# Micromouse.net
KiCad netlist of a schematic drawn in EAGLE
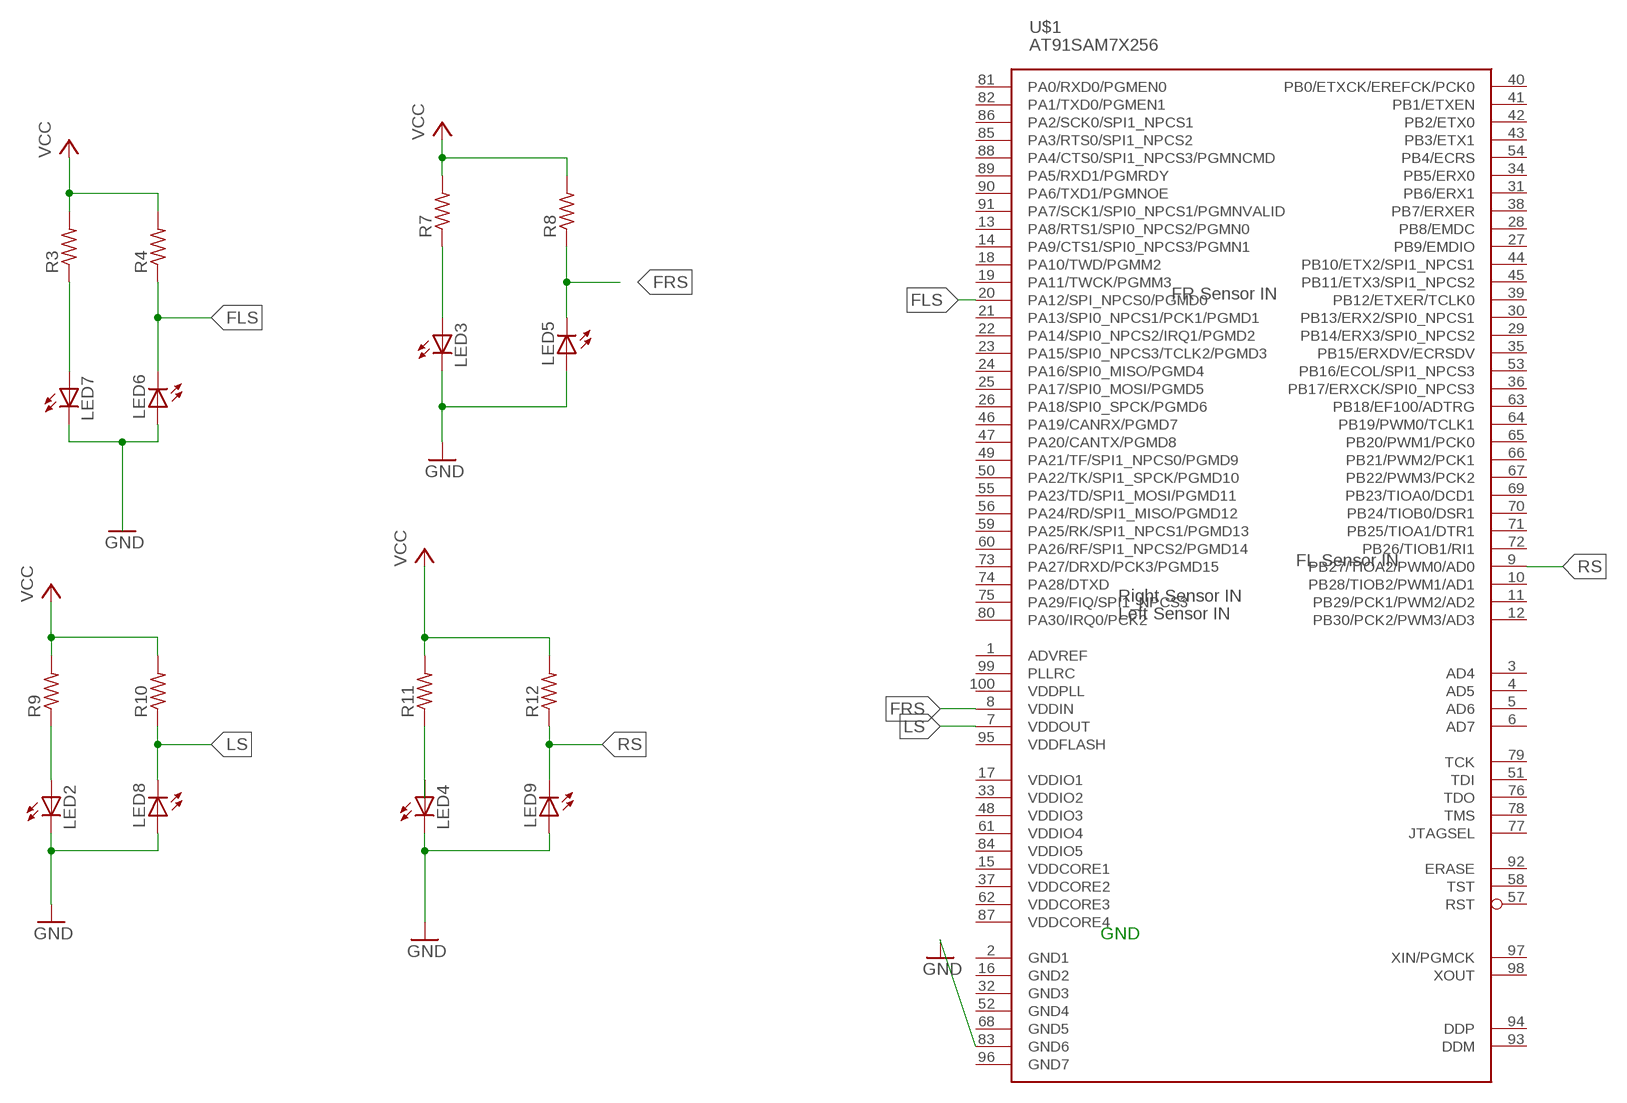
[diagram p0: schematic, sheet 1]

(export (version "E")
  (design (tool "Eeschema 10.0.6"))
  (components
    (comp (ref "LED2")
      (value "LED5MM")
      (footprint "eagle-import:LED5MM")
      (libsource (lib "eagle-import") (part "LED5MM"))
    )
    (comp (ref "LED3")
      (value "LED5MM")
      (footprint "eagle-import:LED5MM")
      (libsource (lib "eagle-import") (part "LED5MM"))
    )
    (comp (ref "LED4")
      (value "LED5MM")
      (footprint "eagle-import:LED5MM")
      (libsource (lib "eagle-import") (part "LED5MM"))
    )
    (comp (ref "LED5")
      (value "LED5MM")
      (footprint "eagle-import:LED5MM")
      (libsource (lib "eagle-import") (part "LED5MM"))
    )
    (comp (ref "LED6")
      (value "LED5MM")
      (footprint "eagle-import:LED5MM")
      (libsource (lib "eagle-import") (part "LED5MM"))
    )
    (comp (ref "LED7")
      (value "LED5MM")
      (footprint "eagle-import:LED5MM")
      (libsource (lib "eagle-import") (part "LED5MM"))
    )
    (comp (ref "LED8")
      (value "LED5MM")
      (footprint "eagle-import:LED5MM")
      (libsource (lib "eagle-import") (part "LED5MM"))
    )
    (comp (ref "LED9")
      (value "LED5MM")
      (footprint "eagle-import:LED5MM")
      (libsource (lib "eagle-import") (part "LED5MM"))
    )
    (comp (ref "R3")
      (value "R-US_R0805")
      (footprint "eagle-import:R0805")
      (libsource (lib "eagle-import") (part "R-US_R0805"))
    )
    (comp (ref "R4")
      (value "R-US_R0805")
      (footprint "eagle-import:R0805")
      (libsource (lib "eagle-import") (part "R-US_R0805"))
    )
    (comp (ref "R7")
      (value "R-US_R0805")
      (footprint "eagle-import:R0805")
      (libsource (lib "eagle-import") (part "R-US_R0805"))
    )
    (comp (ref "R8")
      (value "R-US_R0805")
      (footprint "eagle-import:R0805")
      (libsource (lib "eagle-import") (part "R-US_R0805"))
    )
    (comp (ref "R9")
      (value "R-US_R0805")
      (footprint "eagle-import:R0805")
      (libsource (lib "eagle-import") (part "R-US_R0805"))
    )
    (comp (ref "R10")
      (value "R-US_R0805")
      (footprint "eagle-import:R0805")
      (libsource (lib "eagle-import") (part "R-US_R0805"))
    )
    (comp (ref "R11")
      (value "R-US_R0805")
      (footprint "eagle-import:R0805")
      (libsource (lib "eagle-import") (part "R-US_R0805"))
    )
    (comp (ref "R12")
      (value "R-US_R0805")
      (footprint "eagle-import:R0805")
      (libsource (lib "eagle-import") (part "R-US_R0805"))
    )
    (comp (ref "U$1")
      (value "AT91SAM7X256")
      (footprint "eagle-import:LQFP100")
      (libsource (lib "eagle-import") (part "AT91SAM7X256"))
    )
  )
  (nets
    (net (code "1") (name "FLS") (class "Default")
      (node (ref "LED6") (pin "K") (pinfunction "C_K") (pintype "passive"))
      (node (ref "R4") (pin "1") (pinfunction "1_1") (pintype "passive"))
      (node (ref "U$1") (pin "20") (pinfunction "PA12/SPI_NPCS0/PGMD0_20") (pintype "bidirectional"))
    )
    (net (code "2") (name "FRS") (class "Default")
      (node (ref "LED5") (pin "K") (pinfunction "C_K") (pintype "passive"))
      (node (ref "R8") (pin "1") (pinfunction "1_1") (pintype "passive"))
      (node (ref "U$1") (pin "8") (pinfunction "VDDIN_8") (pintype "bidirectional"))
    )
    (net (code "3") (name "GND") (class "Default")
      (node (ref "LED2") (pin "K") (pinfunction "C_K") (pintype "passive"))
      (node (ref "LED3") (pin "K") (pinfunction "C_K") (pintype "passive"))
      (node (ref "LED4") (pin "K") (pinfunction "C_K") (pintype "passive"))
      (node (ref "LED5") (pin "A") (pinfunction "A_A") (pintype "passive"))
      (node (ref "LED8") (pin "A") (pinfunction "A_A") (pintype "passive"))
      (node (ref "LED9") (pin "A") (pinfunction "A_A") (pintype "passive"))
      (node (ref "U$1") (pin "83") (pinfunction "GND6_83") (pintype "bidirectional"))
    )
    (net (code "4") (name "LS") (class "Default")
      (node (ref "LED8") (pin "K") (pinfunction "C_K") (pintype "passive"))
      (node (ref "R10") (pin "1") (pinfunction "1_1") (pintype "passive"))
      (node (ref "U$1") (pin "7") (pinfunction "VDDOUT_7") (pintype "bidirectional"))
    )
    (net (code "5") (name "Net-(LED2-PadA)") (class "Default")
      (node (ref "LED2") (pin "A") (pinfunction "A_A") (pintype "passive"))
      (node (ref "R9") (pin "1") (pinfunction "1_1") (pintype "passive"))
    )
    (net (code "6") (name "Net-(LED3-PadA)") (class "Default")
      (node (ref "LED3") (pin "A") (pinfunction "A_A") (pintype "passive"))
      (node (ref "R7") (pin "1") (pinfunction "1_1") (pintype "passive"))
    )
    (net (code "7") (name "Net-(LED7-C)") (class "Default")
      (node (ref "LED6") (pin "A") (pinfunction "A_A") (pintype "passive"))
      (node (ref "LED7") (pin "K") (pinfunction "C_K") (pintype "passive"))
    )
    (net (code "8") (name "Net-(LED7-PadA)") (class "Default")
      (node (ref "LED7") (pin "A") (pinfunction "A_A") (pintype "passive"))
      (node (ref "R3") (pin "1") (pinfunction "1_1") (pintype "passive"))
    )
    (net (code "9") (name "RS") (class "Default")
      (node (ref "LED9") (pin "K") (pinfunction "C_K") (pintype "passive"))
      (node (ref "R12") (pin "1") (pinfunction "1_1") (pintype "passive"))
      (node (ref "U$1") (pin "9") (pinfunction "PB27/TIOA2/PWM0/AD0_9") (pintype "bidirectional"))
    )
    (net (code "10") (name "VCC") (class "Default")
      (node (ref "R10") (pin "2") (pinfunction "2_2") (pintype "passive"))
      (node (ref "R11") (pin "2") (pinfunction "2_2") (pintype "passive"))
      (node (ref "R12") (pin "2") (pinfunction "2_2") (pintype "passive"))
      (node (ref "R3") (pin "2") (pinfunction "2_2") (pintype "passive"))
      (node (ref "R4") (pin "2") (pinfunction "2_2") (pintype "passive"))
      (node (ref "R7") (pin "2") (pinfunction "2_2") (pintype "passive"))
      (node (ref "R8") (pin "2") (pinfunction "2_2") (pintype "passive"))
      (node (ref "R9") (pin "2") (pinfunction "2_2") (pintype "passive"))
    )
    (net (code "11") (name "unconnected-(LED4-PadA)") (class "Default")
      (node (ref "LED4") (pin "A") (pinfunction "A_A") (pintype "passive"))
    )
    (net (code "12") (name "unconnected-(R11-Pad1)") (class "Default")
      (node (ref "R11") (pin "1") (pinfunction "1_1") (pintype "passive"))
    )
    (net (code "13") (name "unconnected-(U$1-AD4-Pad3)") (class "Default")
      (node (ref "U$1") (pin "3") (pinfunction "AD4_3") (pintype "bidirectional"))
    )
    (net (code "14") (name "unconnected-(U$1-AD5-Pad4)") (class "Default")
      (node (ref "U$1") (pin "4") (pinfunction "AD5_4") (pintype "bidirectional"))
    )
    (net (code "15") (name "unconnected-(U$1-AD6-Pad5)") (class "Default")
      (node (ref "U$1") (pin "5") (pinfunction "AD6_5") (pintype "bidirectional"))
    )
    (net (code "16") (name "unconnected-(U$1-AD7-Pad6)") (class "Default")
      (node (ref "U$1") (pin "6") (pinfunction "AD7_6") (pintype "bidirectional"))
    )
    (net (code "17") (name "unconnected-(U$1-ADVREF-Pad1)") (class "Default")
      (node (ref "U$1") (pin "1") (pinfunction "ADVREF_1") (pintype "bidirectional"))
    )
    (net (code "18") (name "unconnected-(U$1-DDM-Pad93)") (class "Default")
      (node (ref "U$1") (pin "93") (pinfunction "DDM_93") (pintype "bidirectional"))
    )
    (net (code "19") (name "unconnected-(U$1-DDP-Pad94)") (class "Default")
      (node (ref "U$1") (pin "94") (pinfunction "DDP_94") (pintype "bidirectional"))
    )
    (net (code "20") (name "unconnected-(U$1-ERASE-Pad92)") (class "Default")
      (node (ref "U$1") (pin "92") (pinfunction "ERASE_92") (pintype "bidirectional"))
    )
    (net (code "21") (name "unconnected-(U$1-GND1-Pad2)") (class "Default")
      (node (ref "U$1") (pin "2") (pinfunction "GND1_2") (pintype "bidirectional"))
    )
    (net (code "22") (name "unconnected-(U$1-GND2-Pad16)") (class "Default")
      (node (ref "U$1") (pin "16") (pinfunction "GND2_16") (pintype "bidirectional"))
    )
    (net (code "23") (name "unconnected-(U$1-GND3-Pad32)") (class "Default")
      (node (ref "U$1") (pin "32") (pinfunction "GND3_32") (pintype "bidirectional"))
    )
    (net (code "24") (name "unconnected-(U$1-GND4-Pad52)") (class "Default")
      (node (ref "U$1") (pin "52") (pinfunction "GND4_52") (pintype "bidirectional"))
    )
    (net (code "25") (name "unconnected-(U$1-GND5-Pad68)") (class "Default")
      (node (ref "U$1") (pin "68") (pinfunction "GND5_68") (pintype "bidirectional"))
    )
    (net (code "26") (name "unconnected-(U$1-GND7-Pad96)") (class "Default")
      (node (ref "U$1") (pin "96") (pinfunction "GND7_96") (pintype "bidirectional"))
    )
    (net (code "27") (name "unconnected-(U$1-JTAGSEL-Pad77)") (class "Default")
      (node (ref "U$1") (pin "77") (pinfunction "JTAGSEL_77") (pintype "bidirectional"))
    )
    (net (code "28") (name "unconnected-(U$1-PA0{slash}RXD0{slash}PGMEN0-Pad81)") (class "Default")
      (node (ref "U$1") (pin "81") (pinfunction "PA0/RXD0/PGMEN0_81") (pintype "bidirectional"))
    )
    (net (code "29") (name "unconnected-(U$1-PA1{slash}TXD0{slash}PGMEN1-Pad82)") (class "Default")
      (node (ref "U$1") (pin "82") (pinfunction "PA1/TXD0/PGMEN1_82") (pintype "bidirectional"))
    )
    (net (code "30") (name "unconnected-(U$1-PA2{slash}SCK0{slash}SPI1_NPCS1-Pad86)") (class "Default")
      (node (ref "U$1") (pin "86") (pinfunction "PA2/SCK0/SPI1_NPCS1_86") (pintype "bidirectional"))
    )
    (net (code "31") (name "unconnected-(U$1-PA3{slash}RTS0{slash}SPI1_NPCS2-Pad85)") (class "Default")
      (node (ref "U$1") (pin "85") (pinfunction "PA3/RTS0/SPI1_NPCS2_85") (pintype "bidirectional"))
    )
    (net (code "32") (name "unconnected-(U$1-PA4{slash}CTS0{slash}SPI1_NPCS3{slash}PGMNCMD-Pad88)") (class "Default")
      (node (ref "U$1") (pin "88") (pinfunction "PA4/CTS0/SPI1_NPCS3/PGMNCMD_88") (pintype "bidirectional"))
    )
    (net (code "33") (name "unconnected-(U$1-PA5{slash}RXD1{slash}PGMRDY-Pad89)") (class "Default")
      (node (ref "U$1") (pin "89") (pinfunction "PA5/RXD1/PGMRDY_89") (pintype "bidirectional"))
    )
    (net (code "34") (name "unconnected-(U$1-PA6{slash}TXD1{slash}PGMNOE-Pad90)") (class "Default")
      (node (ref "U$1") (pin "90") (pinfunction "PA6/TXD1/PGMNOE_90") (pintype "bidirectional"))
    )
    (net (code "35") (name "unconnected-(U$1-PA7{slash}SCK1{slash}SPI0_NPCS1{slash}PGMNVALID-Pad91)") (class "Default")
      (node (ref "U$1") (pin "91") (pinfunction "PA7/SCK1/SPI0_NPCS1/PGMNVALID_91") (pintype "bidirectional"))
    )
    (net (code "36") (name "unconnected-(U$1-PA8{slash}RTS1{slash}SPI0_NPCS2{slash}PGMN0-Pad13)") (class "Default")
      (node (ref "U$1") (pin "13") (pinfunction "PA8/RTS1/SPI0_NPCS2/PGMN0_13") (pintype "bidirectional"))
    )
    (net (code "37") (name "unconnected-(U$1-PA9{slash}CTS1{slash}SPI0_NPCS3{slash}PGMN1-Pad14)") (class "Default")
      (node (ref "U$1") (pin "14") (pinfunction "PA9/CTS1/SPI0_NPCS3/PGMN1_14") (pintype "bidirectional"))
    )
    (net (code "38") (name "unconnected-(U$1-PA10{slash}TWD{slash}PGMM2-Pad18)") (class "Default")
      (node (ref "U$1") (pin "18") (pinfunction "PA10/TWD/PGMM2_18") (pintype "bidirectional"))
    )
    (net (code "39") (name "unconnected-(U$1-PA11{slash}TWCK{slash}PGMM3-Pad19)") (class "Default")
      (node (ref "U$1") (pin "19") (pinfunction "PA11/TWCK/PGMM3_19") (pintype "bidirectional"))
    )
    (net (code "40") (name "unconnected-(U$1-PA13{slash}SPI0_NPCS1{slash}PCK1{slash}PGMD1-Pad21)") (class "Default")
      (node (ref "U$1") (pin "21") (pinfunction "PA13/SPI0_NPCS1/PCK1/PGMD1_21") (pintype "bidirectional"))
    )
    (net (code "41") (name "unconnected-(U$1-PA14{slash}SPI0_NPCS2{slash}IRQ1{slash}PGMD2-Pad22)") (class "Default")
      (node (ref "U$1") (pin "22") (pinfunction "PA14/SPI0_NPCS2/IRQ1/PGMD2_22") (pintype "bidirectional"))
    )
    (net (code "42") (name "unconnected-(U$1-PA15{slash}SPI0_NPCS3{slash}TCLK2{slash}PGMD3-Pad23)") (class "Default")
      (node (ref "U$1") (pin "23") (pinfunction "PA15/SPI0_NPCS3/TCLK2/PGMD3_23") (pintype "bidirectional"))
    )
    (net (code "43") (name "unconnected-(U$1-PA16{slash}SPI0_MISO{slash}PGMD4-Pad24)") (class "Default")
      (node (ref "U$1") (pin "24") (pinfunction "PA16/SPI0_MISO/PGMD4_24") (pintype "bidirectional"))
    )
    (net (code "44") (name "unconnected-(U$1-PA17{slash}SPI0_MOSI{slash}PGMD5-Pad25)") (class "Default")
      (node (ref "U$1") (pin "25") (pinfunction "PA17/SPI0_MOSI/PGMD5_25") (pintype "bidirectional"))
    )
    (net (code "45") (name "unconnected-(U$1-PA18{slash}SPI0_SPCK{slash}PGMD6-Pad26)") (class "Default")
      (node (ref "U$1") (pin "26") (pinfunction "PA18/SPI0_SPCK/PGMD6_26") (pintype "bidirectional"))
    )
    (net (code "46") (name "unconnected-(U$1-PA19{slash}CANRX{slash}PGMD7-Pad46)") (class "Default")
      (node (ref "U$1") (pin "46") (pinfunction "PA19/CANRX/PGMD7_46") (pintype "bidirectional"))
    )
    (net (code "47") (name "unconnected-(U$1-PA20{slash}CANTX{slash}PGMD8-Pad47)") (class "Default")
      (node (ref "U$1") (pin "47") (pinfunction "PA20/CANTX/PGMD8_47") (pintype "bidirectional"))
    )
    (net (code "48") (name "unconnected-(U$1-PA21{slash}TF{slash}SPI1_NPCS0{slash}PGMD9-Pad49)") (class "Default")
      (node (ref "U$1") (pin "49") (pinfunction "PA21/TF/SPI1_NPCS0/PGMD9_49") (pintype "bidirectional"))
    )
    (net (code "49") (name "unconnected-(U$1-PA22{slash}TK{slash}SPI1_SPCK{slash}PGMD10-Pad50)") (class "Default")
      (node (ref "U$1") (pin "50") (pinfunction "PA22/TK/SPI1_SPCK/PGMD10_50") (pintype "bidirectional"))
    )
    (net (code "50") (name "unconnected-(U$1-PA23{slash}TD{slash}SPI1_MOSI{slash}PGMD11-Pad55)") (class "Default")
      (node (ref "U$1") (pin "55") (pinfunction "PA23/TD/SPI1_MOSI/PGMD11_55") (pintype "bidirectional"))
    )
    (net (code "51") (name "unconnected-(U$1-PA24{slash}RD{slash}SPI1_MISO{slash}PGMD12-Pad56)") (class "Default")
      (node (ref "U$1") (pin "56") (pinfunction "PA24/RD/SPI1_MISO/PGMD12_56") (pintype "bidirectional"))
    )
    (net (code "52") (name "unconnected-(U$1-PA25{slash}RK{slash}SPI1_NPCS1{slash}PGMD13-Pad59)") (class "Default")
      (node (ref "U$1") (pin "59") (pinfunction "PA25/RK/SPI1_NPCS1/PGMD13_59") (pintype "bidirectional"))
    )
    (net (code "53") (name "unconnected-(U$1-PA26{slash}RF{slash}SPI1_NPCS2{slash}PGMD14-Pad60)") (class "Default")
      (node (ref "U$1") (pin "60") (pinfunction "PA26/RF/SPI1_NPCS2/PGMD14_60") (pintype "bidirectional"))
    )
    (net (code "54") (name "unconnected-(U$1-PA27{slash}DRXD{slash}PCK3{slash}PGMD15-Pad73)") (class "Default")
      (node (ref "U$1") (pin "73") (pinfunction "PA27/DRXD/PCK3/PGMD15_73") (pintype "bidirectional"))
    )
    (net (code "55") (name "unconnected-(U$1-PA28{slash}DTXD-Pad74)") (class "Default")
      (node (ref "U$1") (pin "74") (pinfunction "PA28/DTXD_74") (pintype "bidirectional"))
    )
    (net (code "56") (name "unconnected-(U$1-PA29{slash}FIQ{slash}SPI1_NPCS3-Pad75)") (class "Default")
      (node (ref "U$1") (pin "75") (pinfunction "PA29/FIQ/SPI1_NPCS3_75") (pintype "bidirectional"))
    )
    (net (code "57") (name "unconnected-(U$1-PA30{slash}IRQ0{slash}PCK2-Pad80)") (class "Default")
      (node (ref "U$1") (pin "80") (pinfunction "PA30/IRQ0/PCK2_80") (pintype "bidirectional"))
    )
    (net (code "58") (name "unconnected-(U$1-PB0{slash}ETXCK{slash}EREFCK{slash}PCK0-Pad40)") (class "Default")
      (node (ref "U$1") (pin "40") (pinfunction "PB0/ETXCK/EREFCK/PCK0_40") (pintype "bidirectional"))
    )
    (net (code "59") (name "unconnected-(U$1-PB1{slash}ETXEN-Pad41)") (class "Default")
      (node (ref "U$1") (pin "41") (pinfunction "PB1/ETXEN_41") (pintype "bidirectional"))
    )
    (net (code "60") (name "unconnected-(U$1-PB2{slash}ETX0-Pad42)") (class "Default")
      (node (ref "U$1") (pin "42") (pinfunction "PB2/ETX0_42") (pintype "bidirectional"))
    )
    (net (code "61") (name "unconnected-(U$1-PB3{slash}ETX1-Pad43)") (class "Default")
      (node (ref "U$1") (pin "43") (pinfunction "PB3/ETX1_43") (pintype "bidirectional"))
    )
    (net (code "62") (name "unconnected-(U$1-PB4{slash}ECRS-Pad54)") (class "Default")
      (node (ref "U$1") (pin "54") (pinfunction "PB4/ECRS_54") (pintype "bidirectional"))
    )
    (net (code "63") (name "unconnected-(U$1-PB5{slash}ERX0-Pad34)") (class "Default")
      (node (ref "U$1") (pin "34") (pinfunction "PB5/ERX0_34") (pintype "bidirectional"))
    )
    (net (code "64") (name "unconnected-(U$1-PB6{slash}ERX1-Pad31)") (class "Default")
      (node (ref "U$1") (pin "31") (pinfunction "PB6/ERX1_31") (pintype "bidirectional"))
    )
    (net (code "65") (name "unconnected-(U$1-PB7{slash}ERXER-Pad38)") (class "Default")
      (node (ref "U$1") (pin "38") (pinfunction "PB7/ERXER_38") (pintype "bidirectional"))
    )
    (net (code "66") (name "unconnected-(U$1-PB8{slash}EMDC-Pad28)") (class "Default")
      (node (ref "U$1") (pin "28") (pinfunction "PB8/EMDC_28") (pintype "bidirectional"))
    )
    (net (code "67") (name "unconnected-(U$1-PB9{slash}EMDIO-Pad27)") (class "Default")
      (node (ref "U$1") (pin "27") (pinfunction "PB9/EMDIO_27") (pintype "bidirectional"))
    )
    (net (code "68") (name "unconnected-(U$1-PB10{slash}ETX2{slash}SPI1_NPCS1-Pad44)") (class "Default")
      (node (ref "U$1") (pin "44") (pinfunction "PB10/ETX2/SPI1_NPCS1_44") (pintype "bidirectional"))
    )
    (net (code "69") (name "unconnected-(U$1-PB11{slash}ETX3{slash}SPI1_NPCS2-Pad45)") (class "Default")
      (node (ref "U$1") (pin "45") (pinfunction "PB11/ETX3/SPI1_NPCS2_45") (pintype "bidirectional"))
    )
    (net (code "70") (name "unconnected-(U$1-PB12{slash}ETXER{slash}TCLK0-Pad39)") (class "Default")
      (node (ref "U$1") (pin "39") (pinfunction "PB12/ETXER/TCLK0_39") (pintype "bidirectional"))
    )
    (net (code "71") (name "unconnected-(U$1-PB13{slash}ERX2{slash}SPI0_NPCS1-Pad30)") (class "Default")
      (node (ref "U$1") (pin "30") (pinfunction "PB13/ERX2/SPI0_NPCS1_30") (pintype "bidirectional"))
    )
    (net (code "72") (name "unconnected-(U$1-PB14{slash}ERX3{slash}SPI0_NPCS2-Pad29)") (class "Default")
      (node (ref "U$1") (pin "29") (pinfunction "PB14/ERX3/SPI0_NPCS2_29") (pintype "bidirectional"))
    )
    (net (code "73") (name "unconnected-(U$1-PB15{slash}ERXDV{slash}ECRSDV-Pad35)") (class "Default")
      (node (ref "U$1") (pin "35") (pinfunction "PB15/ERXDV/ECRSDV_35") (pintype "bidirectional"))
    )
    (net (code "74") (name "unconnected-(U$1-PB16{slash}ECOL{slash}SPI1_NPCS3-Pad53)") (class "Default")
      (node (ref "U$1") (pin "53") (pinfunction "PB16/ECOL/SPI1_NPCS3_53") (pintype "bidirectional"))
    )
    (net (code "75") (name "unconnected-(U$1-PB17{slash}ERXCK{slash}SPI0_NPCS3-Pad36)") (class "Default")
      (node (ref "U$1") (pin "36") (pinfunction "PB17/ERXCK/SPI0_NPCS3_36") (pintype "bidirectional"))
    )
    (net (code "76") (name "unconnected-(U$1-PB18{slash}EF100{slash}ADTRG-Pad63)") (class "Default")
      (node (ref "U$1") (pin "63") (pinfunction "PB18/EF100/ADTRG_63") (pintype "bidirectional"))
    )
    (net (code "77") (name "unconnected-(U$1-PB19{slash}PWM0{slash}TCLK1-Pad64)") (class "Default")
      (node (ref "U$1") (pin "64") (pinfunction "PB19/PWM0/TCLK1_64") (pintype "bidirectional"))
    )
    (net (code "78") (name "unconnected-(U$1-PB20{slash}PWM1{slash}PCK0-Pad65)") (class "Default")
      (node (ref "U$1") (pin "65") (pinfunction "PB20/PWM1/PCK0_65") (pintype "bidirectional"))
    )
    (net (code "79") (name "unconnected-(U$1-PB21{slash}PWM2{slash}PCK1-Pad66)") (class "Default")
      (node (ref "U$1") (pin "66") (pinfunction "PB21/PWM2/PCK1_66") (pintype "bidirectional"))
    )
    (net (code "80") (name "unconnected-(U$1-PB22{slash}PWM3{slash}PCK2-Pad67)") (class "Default")
      (node (ref "U$1") (pin "67") (pinfunction "PB22/PWM3/PCK2_67") (pintype "bidirectional"))
    )
    (net (code "81") (name "unconnected-(U$1-PB23{slash}TIOA0{slash}DCD1-Pad69)") (class "Default")
      (node (ref "U$1") (pin "69") (pinfunction "PB23/TIOA0/DCD1_69") (pintype "bidirectional"))
    )
    (net (code "82") (name "unconnected-(U$1-PB24{slash}TIOB0{slash}DSR1-Pad70)") (class "Default")
      (node (ref "U$1") (pin "70") (pinfunction "PB24/TIOB0/DSR1_70") (pintype "bidirectional"))
    )
    (net (code "83") (name "unconnected-(U$1-PB25{slash}TIOA1{slash}DTR1-Pad71)") (class "Default")
      (node (ref "U$1") (pin "71") (pinfunction "PB25/TIOA1/DTR1_71") (pintype "bidirectional"))
    )
    (net (code "84") (name "unconnected-(U$1-PB26{slash}TIOB1{slash}RI1-Pad72)") (class "Default")
      (node (ref "U$1") (pin "72") (pinfunction "PB26/TIOB1/RI1_72") (pintype "bidirectional"))
    )
    (net (code "85") (name "unconnected-(U$1-PB28{slash}TIOB2{slash}PWM1{slash}AD1-Pad10)") (class "Default")
      (node (ref "U$1") (pin "10") (pinfunction "PB28/TIOB2/PWM1/AD1_10") (pintype "bidirectional"))
    )
    (net (code "86") (name "unconnected-(U$1-PB29{slash}PCK1{slash}PWM2{slash}AD2-Pad11)") (class "Default")
      (node (ref "U$1") (pin "11") (pinfunction "PB29/PCK1/PWM2/AD2_11") (pintype "bidirectional"))
    )
    (net (code "87") (name "unconnected-(U$1-PB30{slash}PCK2{slash}PWM3{slash}AD3-Pad12)") (class "Default")
      (node (ref "U$1") (pin "12") (pinfunction "PB30/PCK2/PWM3/AD3_12") (pintype "bidirectional"))
    )
    (net (code "88") (name "unconnected-(U$1-PLLRC-Pad99)") (class "Default")
      (node (ref "U$1") (pin "99") (pinfunction "PLLRC_99") (pintype "bidirectional"))
    )
    (net (code "89") (name "unconnected-(U$1-RST-Pad57)") (class "Default")
      (node (ref "U$1") (pin "57") (pinfunction "RST_57") (pintype "bidirectional"))
    )
    (net (code "90") (name "unconnected-(U$1-TCK-Pad79)") (class "Default")
      (node (ref "U$1") (pin "79") (pinfunction "TCK_79") (pintype "bidirectional"))
    )
    (net (code "91") (name "unconnected-(U$1-TDI-Pad51)") (class "Default")
      (node (ref "U$1") (pin "51") (pinfunction "TDI_51") (pintype "bidirectional"))
    )
    (net (code "92") (name "unconnected-(U$1-TDO-Pad76)") (class "Default")
      (node (ref "U$1") (pin "76") (pinfunction "TDO_76") (pintype "bidirectional"))
    )
    (net (code "93") (name "unconnected-(U$1-TMS-Pad78)") (class "Default")
      (node (ref "U$1") (pin "78") (pinfunction "TMS_78") (pintype "bidirectional"))
    )
    (net (code "94") (name "unconnected-(U$1-TST-Pad58)") (class "Default")
      (node (ref "U$1") (pin "58") (pinfunction "TST_58") (pintype "bidirectional"))
    )
    (net (code "95") (name "unconnected-(U$1-VDDCORE1-Pad15)") (class "Default")
      (node (ref "U$1") (pin "15") (pinfunction "VDDCORE1_15") (pintype "bidirectional"))
    )
    (net (code "96") (name "unconnected-(U$1-VDDCORE2-Pad37)") (class "Default")
      (node (ref "U$1") (pin "37") (pinfunction "VDDCORE2_37") (pintype "bidirectional"))
    )
    (net (code "97") (name "unconnected-(U$1-VDDCORE3-Pad62)") (class "Default")
      (node (ref "U$1") (pin "62") (pinfunction "VDDCORE3_62") (pintype "bidirectional"))
    )
    (net (code "98") (name "unconnected-(U$1-VDDCORE4-Pad87)") (class "Default")
      (node (ref "U$1") (pin "87") (pinfunction "VDDCORE4_87") (pintype "bidirectional"))
    )
    (net (code "99") (name "unconnected-(U$1-VDDFLASH-Pad95)") (class "Default")
      (node (ref "U$1") (pin "95") (pinfunction "VDDFLASH_95") (pintype "bidirectional"))
    )
    (net (code "100") (name "unconnected-(U$1-VDDIO1-Pad17)") (class "Default")
      (node (ref "U$1") (pin "17") (pinfunction "VDDIO1_17") (pintype "bidirectional"))
    )
    (net (code "101") (name "unconnected-(U$1-VDDIO2-Pad33)") (class "Default")
      (node (ref "U$1") (pin "33") (pinfunction "VDDIO2_33") (pintype "bidirectional"))
    )
    (net (code "102") (name "unconnected-(U$1-VDDIO3-Pad48)") (class "Default")
      (node (ref "U$1") (pin "48") (pinfunction "VDDIO3_48") (pintype "bidirectional"))
    )
    (net (code "103") (name "unconnected-(U$1-VDDIO4-Pad61)") (class "Default")
      (node (ref "U$1") (pin "61") (pinfunction "VDDIO4_61") (pintype "bidirectional"))
    )
    (net (code "104") (name "unconnected-(U$1-VDDIO5-Pad84)") (class "Default")
      (node (ref "U$1") (pin "84") (pinfunction "VDDIO5_84") (pintype "bidirectional"))
    )
    (net (code "105") (name "unconnected-(U$1-VDDPLL-Pad100)") (class "Default")
      (node (ref "U$1") (pin "100") (pinfunction "VDDPLL_100") (pintype "bidirectional"))
    )
    (net (code "106") (name "unconnected-(U$1-XIN{slash}PGMCK-Pad97)") (class "Default")
      (node (ref "U$1") (pin "97") (pinfunction "XIN/PGMCK_97") (pintype "bidirectional"))
    )
    (net (code "107") (name "unconnected-(U$1-XOUT-Pad98)") (class "Default")
      (node (ref "U$1") (pin "98") (pinfunction "XOUT_98") (pintype "bidirectional"))
    )
  )
)
